# 477.net
KiCad netlist of a schematic drawn in EAGLE
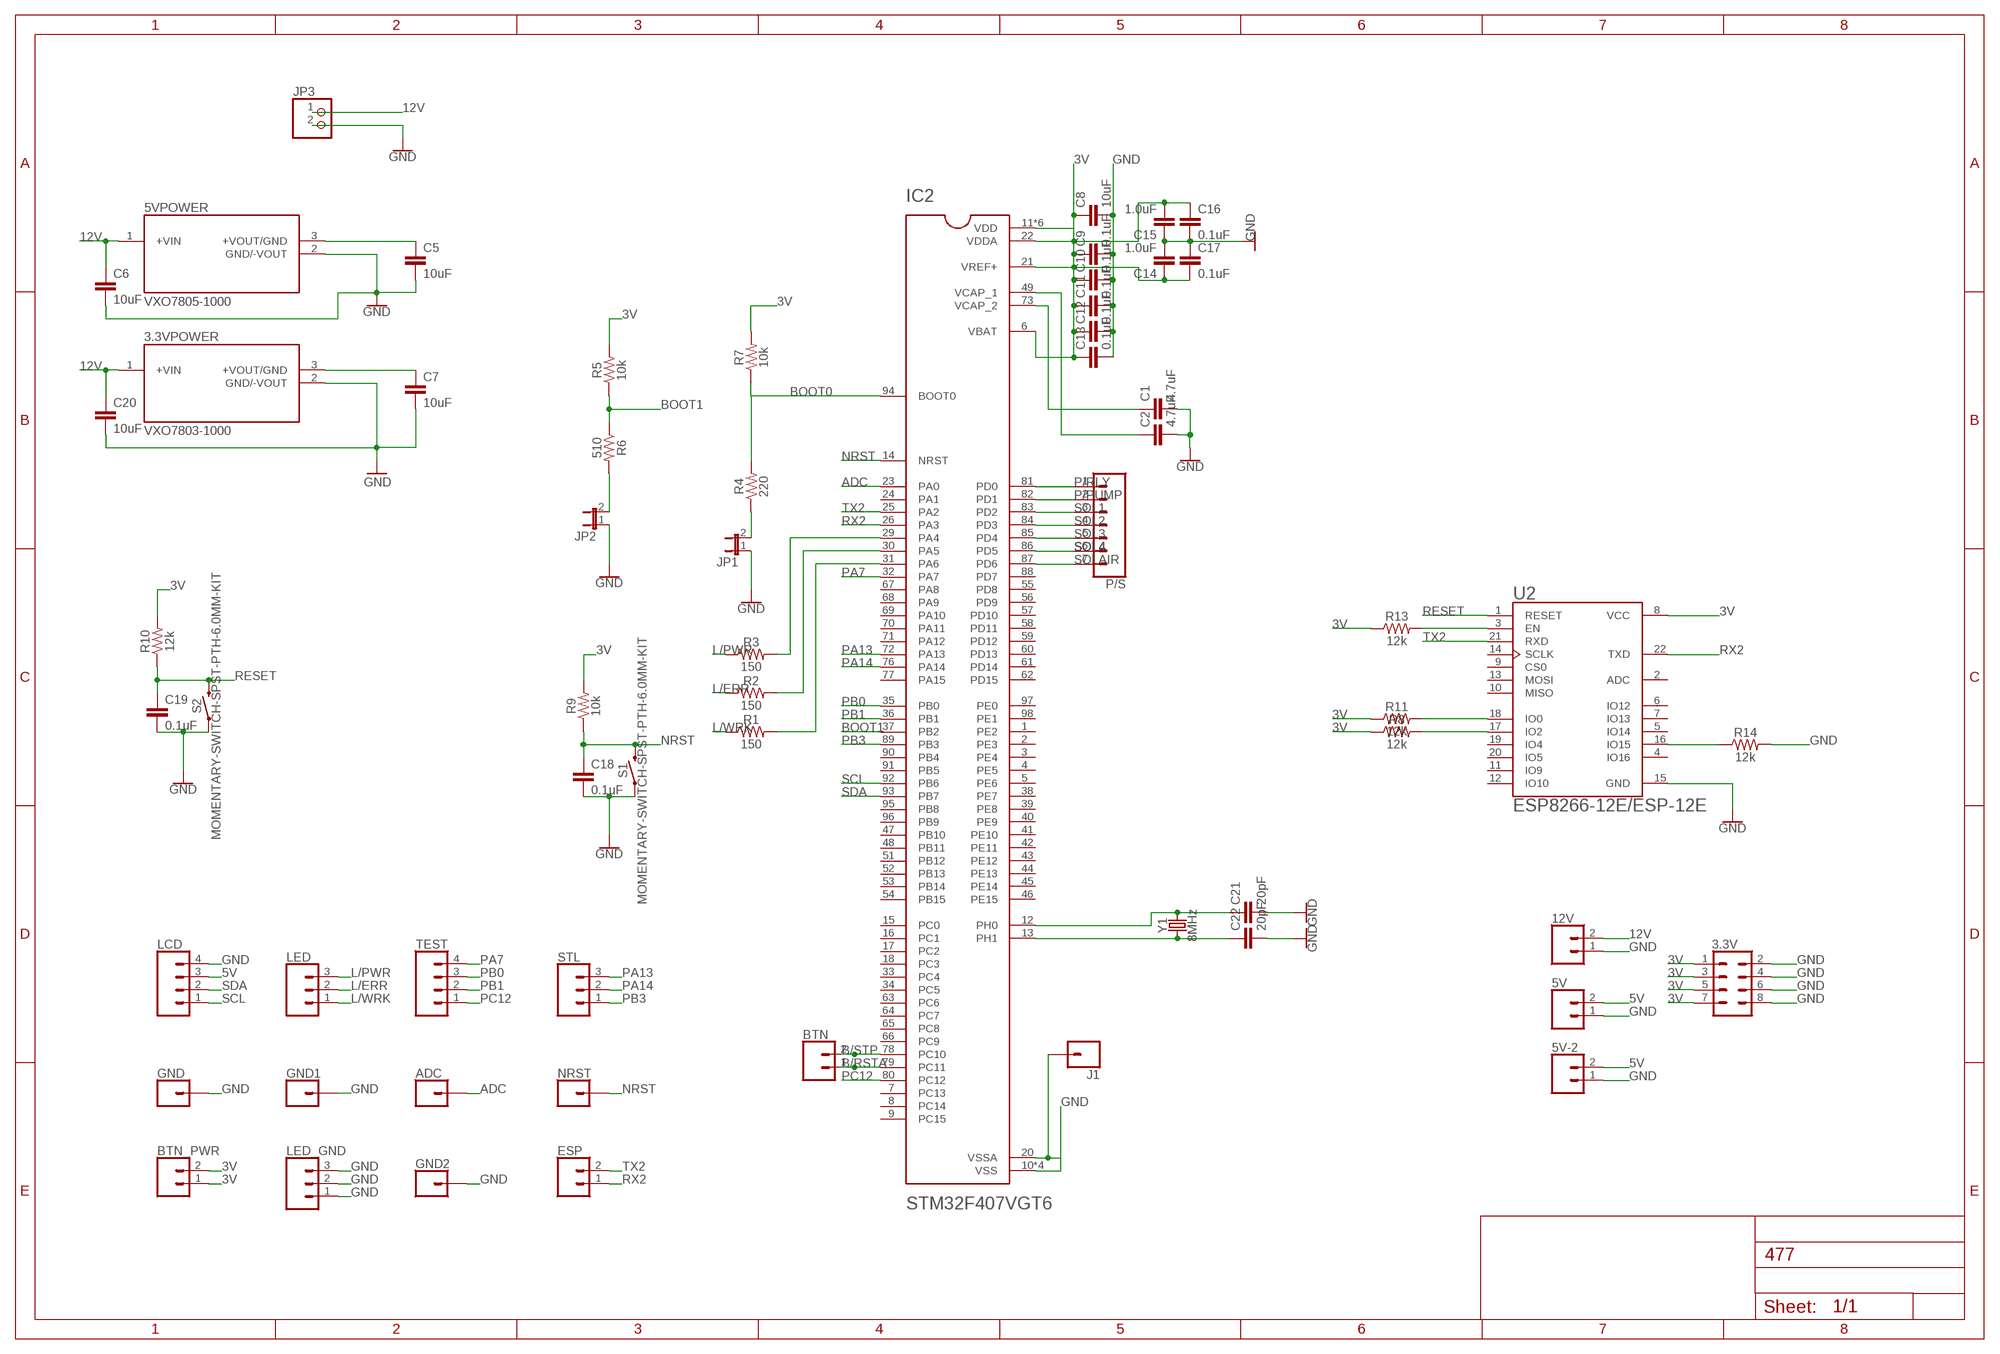
[diagram p0: schematic, sheet 1]

(export (version "E")
  (design (tool "Eeschema 10.0.6"))
  (components
    (comp (ref "3.3V")
      (value "CONN_04X2")
      (footprint "eagle-import:2X4")
      (libsource (lib "eagle-import") (part "CONN_04X2"))
    )
    (comp (ref "3.3VPOWER")
      (value "VXO7803-1000")
      (footprint "eagle-import:CONV_VXO7803-1000")
      (fields (field (name "MF") "CUI Inc."))
      (libsource (lib "eagle-import") (part "VXO7803-1000"))
    )
    (comp (ref "5V")
      (value "CONN_02")
      (footprint "eagle-import:1X02")
      (libsource (lib "eagle-import") (part "SparkFun-Connectors_513_CONN_02"))
    )
    (comp (ref "5V-2")
      (value "CONN_02")
      (footprint "eagle-import:1X02")
      (libsource (lib "eagle-import") (part "SparkFun-Connectors_513_CONN_02"))
    )
    (comp (ref "5VPOWER")
      (value "VXO7805-1000")
      (footprint "eagle-import:CONV_VXO7805-1000")
      (fields (field (name "MF") "CUI Inc."))
      (libsource (lib "eagle-import") (part "VXO7805-1000"))
    )
    (comp (ref "12V")
      (value "CONN_02")
      (footprint "eagle-import:1X02")
      (libsource (lib "eagle-import") (part "SparkFun-Connectors_513_CONN_02"))
    )
    (comp (ref "ADC")
      (value "CONN_01")
      (footprint "eagle-import:1X01")
      (libsource (lib "eagle-import") (part "CONN_01"))
    )
    (comp (ref "BTN")
      (value "CONN_02")
      (footprint "eagle-import:1X02")
      (libsource (lib "eagle-import") (part "CONN_02"))
    )
    (comp (ref "BTN_PWR")
      (value "CONN_02")
      (footprint "eagle-import:1X02")
      (libsource (lib "eagle-import") (part "SparkFun-Connectors_513_CONN_02"))
    )
    (comp (ref "C1")
      (value "4.7uF")
      (footprint "eagle-import:0603")
      (libsource (lib "eagle-import") (part "4.7UF0603"))
    )
    (comp (ref "C2")
      (value "4.7uF")
      (footprint "eagle-import:0603")
      (libsource (lib "eagle-import") (part "4.7UF0603"))
    )
    (comp (ref "C5")
      (value "10uF")
      (footprint "eagle-import:0603")
      (libsource (lib "eagle-import") (part "10UF-0603-6.3V-20%"))
    )
    (comp (ref "C6")
      (value "10uF")
      (footprint "eagle-import:0603")
      (libsource (lib "eagle-import") (part "10UF-0603-6.3V-20%"))
    )
    (comp (ref "C7")
      (value "10uF")
      (footprint "eagle-import:0603")
      (libsource (lib "eagle-import") (part "10UF-0603-6.3V-20%"))
    )
    (comp (ref "C8")
      (value "10uF")
      (footprint "eagle-import:0603")
      (libsource (lib "eagle-import") (part "10UF-0603-6.3V-20%"))
    )
    (comp (ref "C9")
      (value "0.1uF")
      (footprint "eagle-import:0402")
      (libsource (lib "eagle-import") (part "0.1UF-0402-16V-10%"))
    )
    (comp (ref "C10")
      (value "0.1uF")
      (footprint "eagle-import:0402")
      (libsource (lib "eagle-import") (part "0.1UF-0402-16V-10%"))
    )
    (comp (ref "C11")
      (value "0.1uF")
      (footprint "eagle-import:0402")
      (libsource (lib "eagle-import") (part "0.1UF-0402-16V-10%"))
    )
    (comp (ref "C12")
      (value "0.1uF")
      (footprint "eagle-import:0402")
      (libsource (lib "eagle-import") (part "0.1UF-0402-16V-10%"))
    )
    (comp (ref "C13")
      (value "0.1uF")
      (footprint "eagle-import:0402")
      (libsource (lib "eagle-import") (part "0.1UF-0402-16V-10%"))
    )
    (comp (ref "C14")
      (value "1.0uF")
      (footprint "eagle-import:0402")
      (libsource (lib "eagle-import") (part "1.0UF-0402-16V-10%"))
    )
    (comp (ref "C15")
      (value "1.0uF")
      (footprint "eagle-import:0402")
      (libsource (lib "eagle-import") (part "1.0UF-0402-16V-10%"))
    )
    (comp (ref "C16")
      (value "0.1uF")
      (footprint "eagle-import:0402")
      (libsource (lib "eagle-import") (part "0.1UF-0402-16V-10%"))
    )
    (comp (ref "C17")
      (value "0.1uF")
      (footprint "eagle-import:0402")
      (libsource (lib "eagle-import") (part "0.1UF-0402-16V-10%"))
    )
    (comp (ref "C18")
      (value "0.1uF")
      (footprint "eagle-import:0402")
      (libsource (lib "eagle-import") (part "0.1UF-0402-16V-10%"))
    )
    (comp (ref "C19")
      (value "0.1uF")
      (footprint "eagle-import:0402")
      (libsource (lib "eagle-import") (part "0.1UF-0402-16V-10%"))
    )
    (comp (ref "C20")
      (value "10uF")
      (footprint "eagle-import:0603")
      (libsource (lib "eagle-import") (part "10UF-0603-6.3V-20%"))
    )
    (comp (ref "C21")
      (value "20pF")
      (footprint "eagle-import:0603")
      (libsource (lib "eagle-import") (part "18PF-0603-50V-5%"))
    )
    (comp (ref "C22")
      (value "20pF")
      (footprint "eagle-import:0603")
      (libsource (lib "eagle-import") (part "18PF-0603-50V-5%"))
    )
    (comp (ref "ESP")
      (value "CONN_02")
      (footprint "eagle-import:1X02")
      (libsource (lib "eagle-import") (part "SparkFun-Connectors_513_CONN_02"))
    )
    (comp (ref "GND")
      (value "CONN_01PTH_NO_SILK_YES_STOP")
      (footprint "eagle-import:1X01_NO_SILK")
      (libsource (lib "eagle-import") (part "CONN_01PTH_NO_SILK_YES_STOP"))
    )
    (comp (ref "GND1")
      (value "CONN_01PTH_NO_SILK_YES_STOP")
      (footprint "eagle-import:1X01_NO_SILK")
      (libsource (lib "eagle-import") (part "CONN_01PTH_NO_SILK_YES_STOP"))
    )
    (comp (ref "GND2")
      (value "CONN_01")
      (footprint "eagle-import:1X01")
      (libsource (lib "eagle-import") (part "CONN_01"))
    )
    (comp (ref "IC2")
      (value "STM32F407VGT6")
      (footprint "eagle-import:QFP50P1600X1600X160-100N")
      (fields (field (name "MF") "STMicroelectronics"))
      (libsource (lib "eagle-import") (part "STM32F407VGT6"))
    )
    (comp (ref "J1")
      (value "CONN_01PTH_NO_SILK_YES_STOP")
      (footprint "eagle-import:1X01_NO_SILK")
      (libsource (lib "eagle-import") (part "CONN_01PTH_NO_SILK_YES_STOP"))
    )
    (comp (ref "JP1")
      (value "JP1E")
      (footprint "eagle-import:JP1")
      (libsource (lib "eagle-import") (part "JP1E"))
    )
    (comp (ref "JP2")
      (value "JP1E")
      (footprint "eagle-import:JP1")
      (libsource (lib "eagle-import") (part "JP1E"))
    )
    (comp (ref "JP3")
      (value "PINHD-1X2")
      (footprint "eagle-import:1X02")
      (libsource (lib "eagle-import") (part "PINHD-1X2"))
    )
    (comp (ref "LCD")
      (value "CONN_04")
      (footprint "eagle-import:1X04")
      (libsource (lib "eagle-import") (part "CONN_04"))
    )
    (comp (ref "LED")
      (value "CONN_03")
      (footprint "eagle-import:1X03")
      (libsource (lib "eagle-import") (part "CONN_03"))
    )
    (comp (ref "LED_GND")
      (value "CONN_03")
      (footprint "eagle-import:1X03")
      (libsource (lib "eagle-import") (part "CONN_03"))
    )
    (comp (ref "NRST")
      (value "CONN_01")
      (footprint "eagle-import:1X01")
      (libsource (lib "eagle-import") (part "CONN_01"))
    )
    (comp (ref "P/S")
      (value "CONN_07")
      (footprint "eagle-import:1X07")
      (libsource (lib "eagle-import") (part "CONN_07"))
    )
    (comp (ref "R1")
      (value "150")
      (footprint "eagle-import:0603")
      (libsource (lib "eagle-import") (part "150OHM-0603-1/10W-1%"))
    )
    (comp (ref "R2")
      (value "150")
      (footprint "eagle-import:0603")
      (libsource (lib "eagle-import") (part "150OHM-0603-1/10W-1%"))
    )
    (comp (ref "R3")
      (value "150")
      (footprint "eagle-import:0603")
      (libsource (lib "eagle-import") (part "150OHM-0603-1/10W-1%"))
    )
    (comp (ref "R4")
      (value "220")
      (footprint "eagle-import:0603")
      (libsource (lib "eagle-import") (part "220OHM-0603-1/10W-1%"))
    )
    (comp (ref "R5")
      (value "10k")
      (footprint "eagle-import:0603")
      (libsource (lib "eagle-import") (part "1KOHM-0603-1/10W-1%"))
    )
    (comp (ref "R6")
      (value "510")
      (footprint "eagle-import:0603")
      (libsource (lib "eagle-import") (part "0.05OHM-0603-1/5W-1%"))
    )
    (comp (ref "R7")
      (value "10k")
      (footprint "eagle-import:0603")
      (libsource (lib "eagle-import") (part "10KOHM-0603-1/10W-1%"))
    )
    (comp (ref "R8")
      (value "12k")
      (footprint "eagle-import:0603")
      (libsource (lib "eagle-import") (part "12KOHM-0603-1/10W-1%"))
    )
    (comp (ref "R9")
      (value "10k")
      (footprint "eagle-import:0603")
      (libsource (lib "eagle-import") (part "10KOHM-0603-1/10W-1%"))
    )
    (comp (ref "R10")
      (value "12k")
      (footprint "eagle-import:0603")
      (libsource (lib "eagle-import") (part "12KOHM-0603-1/10W-1%"))
    )
    (comp (ref "R11")
      (value "12k")
      (footprint "eagle-import:0603")
      (libsource (lib "eagle-import") (part "12KOHM-0603-1/10W-1%"))
    )
    (comp (ref "R13")
      (value "12k")
      (footprint "eagle-import:0603")
      (libsource (lib "eagle-import") (part "12KOHM-0603-1/10W-1%"))
    )
    (comp (ref "R14")
      (value "12k")
      (footprint "eagle-import:0603")
      (libsource (lib "eagle-import") (part "12KOHM-0603-1/10W-1%"))
    )
    (comp (ref "S1")
      (value "MOMENTARY-SWITCH-SPST-PTH-6.0MM-KIT")
      (footprint "eagle-import:TACTILE_SWITCH_PTH_6.0MM_KIT")
      (libsource (lib "eagle-import") (part "MOMENTARY-SWITCH-SPST-PTH-6.0MM-KIT"))
    )
    (comp (ref "S2")
      (value "MOMENTARY-SWITCH-SPST-PTH-6.0MM-KIT")
      (footprint "eagle-import:TACTILE_SWITCH_PTH_6.0MM_KIT")
      (libsource (lib "eagle-import") (part "MOMENTARY-SWITCH-SPST-PTH-6.0MM-KIT"))
    )
    (comp (ref "STL")
      (value "CONN_03")
      (footprint "eagle-import:1X03")
      (libsource (lib "eagle-import") (part "CONN_03"))
    )
    (comp (ref "TEST")
      (value "CONN_04")
      (footprint "eagle-import:1X04")
      (libsource (lib "eagle-import") (part "CONN_04"))
    )
    (comp (ref "U2")
      (value "ESP8266-12E/ESP-12E")
      (footprint "eagle-import:XCVR_ESP8266-12E_ESP-12E")
      (fields (field (name "MF") "AI-Thinker"))
      (libsource (lib "eagle-import") (part "ESP8266-12E/ESP-12E"))
    )
    (comp (ref "Y1")
      (value "8MHz")
      (footprint "eagle-import:HC49UP")
      (libsource (lib "eagle-import") (part "CRYSTAL-8MHZSMD-HC49UP"))
    )
  )
  (nets
    (net (code "1") (name "/3V") (class "Default")
      (node (ref "3.3V") (pin "1") (pinfunction "1_1") (pintype "passive"))
      (node (ref "3.3V") (pin "3") (pinfunction "3_3") (pintype "passive"))
      (node (ref "3.3V") (pin "5") (pinfunction "5_5") (pintype "passive"))
      (node (ref "3.3V") (pin "7") (pinfunction "7_7") (pintype "passive"))
      (node (ref "3.3VPOWER") (pin "3") (pinfunction "+VOUT/GND_3") (pintype "output"))
      (node (ref "BTN_PWR") (pin "1") (pinfunction "1_1") (pintype "passive"))
      (node (ref "BTN_PWR") (pin "2") (pinfunction "2_2") (pintype "passive"))
      (node (ref "C10") (pin "1") (pinfunction "1_1") (pintype "passive"))
      (node (ref "C11") (pin "1") (pinfunction "1_1") (pintype "passive"))
      (node (ref "C12") (pin "1") (pinfunction "1_1") (pintype "passive"))
      (node (ref "C13") (pin "1") (pinfunction "1_1") (pintype "passive"))
      (node (ref "C14") (pin "1") (pinfunction "1_1") (pintype "passive"))
      (node (ref "C15") (pin "2") (pinfunction "2_2") (pintype "passive"))
      (node (ref "C16") (pin "1") (pinfunction "1_1") (pintype "passive"))
      (node (ref "C17") (pin "2") (pinfunction "2_2") (pintype "passive"))
      (node (ref "C7") (pin "1") (pinfunction "1_1") (pintype "passive"))
      (node (ref "C8") (pin "1") (pinfunction "1_1") (pintype "passive"))
      (node (ref "C9") (pin "1") (pinfunction "1_1") (pintype "passive"))
      (node (ref "IC2") (pin "100") (pinfunction "VDD_100") (pintype "power_in"))
      (node (ref "IC2") (pin "11") (pinfunction "VDD_11") (pintype "power_in"))
      (node (ref "IC2") (pin "19") (pinfunction "VDD_19") (pintype "power_in"))
      (node (ref "IC2") (pin "21") (pinfunction "VREF+_21") (pintype "power_in"))
      (node (ref "IC2") (pin "22") (pinfunction "VDDA_22") (pintype "power_in"))
      (node (ref "IC2") (pin "28") (pinfunction "VDD_28") (pintype "power_in"))
      (node (ref "IC2") (pin "50") (pinfunction "VDD_50") (pintype "power_in"))
      (node (ref "IC2") (pin "6") (pinfunction "VBAT_6") (pintype "power_in"))
      (node (ref "IC2") (pin "75") (pinfunction "VDD_75") (pintype "power_in"))
      (node (ref "R10") (pin "2") (pinfunction "2_2") (pintype "passive"))
      (node (ref "R11") (pin "1") (pinfunction "1_1") (pintype "passive"))
      (node (ref "R13") (pin "1") (pinfunction "1_1") (pintype "passive"))
      (node (ref "R5") (pin "2") (pinfunction "2_2") (pintype "passive"))
      (node (ref "R7") (pin "2") (pinfunction "2_2") (pintype "passive"))
      (node (ref "R8") (pin "1") (pinfunction "1_1") (pintype "passive"))
      (node (ref "R9") (pin "2") (pinfunction "2_2") (pintype "passive"))
      (node (ref "U2") (pin "8") (pinfunction "VCC_8") (pintype "power_in"))
    )
    (net (code "2") (name "/5V") (class "Default")
      (node (ref "5V") (pin "2") (pinfunction "2_2") (pintype "passive"))
      (node (ref "5V-2") (pin "2") (pinfunction "2_2") (pintype "passive"))
      (node (ref "5VPOWER") (pin "3") (pinfunction "+VOUT/GND_3") (pintype "output"))
      (node (ref "C5") (pin "1") (pinfunction "1_1") (pintype "passive"))
      (node (ref "LCD") (pin "3") (pinfunction "3_3") (pintype "passive"))
    )
    (net (code "3") (name "/12V") (class "Default")
      (node (ref "12V") (pin "2") (pinfunction "2_2") (pintype "passive"))
      (node (ref "3.3VPOWER") (pin "1") (pinfunction "+VIN_1") (pintype "input"))
      (node (ref "5VPOWER") (pin "1") (pinfunction "+VIN_1") (pintype "input"))
      (node (ref "C20") (pin "1") (pinfunction "1_1") (pintype "passive"))
      (node (ref "C6") (pin "1") (pinfunction "1_1") (pintype "passive"))
      (node (ref "JP3") (pin "1") (pinfunction "1_1") (pintype "passive"))
    )
    (net (code "4") (name "/ADC") (class "Default")
      (node (ref "ADC") (pin "1") (pinfunction "1_1") (pintype "passive"))
      (node (ref "IC2") (pin "23") (pinfunction "PA0_23") (pintype "bidirectional"))
    )
    (net (code "5") (name "/BOOT0") (class "Default")
      (node (ref "IC2") (pin "94") (pinfunction "BOOT0_94") (pintype "input"))
      (node (ref "R4") (pin "2") (pinfunction "2_2") (pintype "passive"))
      (node (ref "R7") (pin "1") (pinfunction "1_1") (pintype "passive"))
    )
    (net (code "6") (name "/BOOT1") (class "Default")
      (node (ref "IC2") (pin "37") (pinfunction "PB2_37") (pintype "bidirectional"))
      (node (ref "R5") (pin "1") (pinfunction "1_1") (pintype "passive"))
      (node (ref "R6") (pin "1") (pinfunction "1_1") (pintype "passive"))
    )
    (net (code "7") (name "/B{slash}RSTA") (class "Default")
      (node (ref "BTN") (pin "1") (pinfunction "1_1") (pintype "passive"))
      (node (ref "IC2") (pin "79") (pinfunction "PC11_79") (pintype "bidirectional"))
    )
    (net (code "8") (name "/B{slash}STP") (class "Default")
      (node (ref "BTN") (pin "2") (pinfunction "2_2") (pintype "passive"))
      (node (ref "IC2") (pin "78") (pinfunction "PC10_78") (pintype "bidirectional"))
    )
    (net (code "9") (name "/L{slash}ERR") (class "Default")
      (node (ref "LED") (pin "2") (pinfunction "2_2") (pintype "passive"))
      (node (ref "R2") (pin "1") (pinfunction "1_1") (pintype "passive"))
    )
    (net (code "10") (name "/L{slash}PWR") (class "Default")
      (node (ref "LED") (pin "3") (pinfunction "3_3") (pintype "passive"))
      (node (ref "R3") (pin "1") (pinfunction "1_1") (pintype "passive"))
    )
    (net (code "11") (name "/L{slash}WRK") (class "Default")
      (node (ref "LED") (pin "1") (pinfunction "1_1") (pintype "passive"))
      (node (ref "R1") (pin "1") (pinfunction "1_1") (pintype "passive"))
    )
    (net (code "12") (name "/NRST") (class "Default")
      (node (ref "C18") (pin "1") (pinfunction "1_1") (pintype "passive"))
      (node (ref "IC2") (pin "14") (pinfunction "NRST_14") (pintype "bidirectional"))
      (node (ref "NRST") (pin "1") (pinfunction "1_1") (pintype "passive"))
      (node (ref "R9") (pin "1") (pinfunction "1_1") (pintype "passive"))
      (node (ref "S1") (pin "3") (pinfunction "2_3") (pintype "passive"))
    )
    (net (code "13") (name "/PA7") (class "Default")
      (node (ref "IC2") (pin "32") (pinfunction "PA7_32") (pintype "bidirectional"))
      (node (ref "TEST") (pin "4") (pinfunction "4_4") (pintype "passive"))
    )
    (net (code "14") (name "/PA13") (class "Default")
      (node (ref "IC2") (pin "72") (pinfunction "PA13_72") (pintype "bidirectional"))
      (node (ref "STL") (pin "3") (pinfunction "3_3") (pintype "passive"))
    )
    (net (code "15") (name "/PA14") (class "Default")
      (node (ref "IC2") (pin "76") (pinfunction "PA14_76") (pintype "bidirectional"))
      (node (ref "STL") (pin "2") (pinfunction "2_2") (pintype "passive"))
    )
    (net (code "16") (name "/PB0") (class "Default")
      (node (ref "IC2") (pin "35") (pinfunction "PB0_35") (pintype "bidirectional"))
      (node (ref "TEST") (pin "3") (pinfunction "3_3") (pintype "passive"))
    )
    (net (code "17") (name "/PB1") (class "Default")
      (node (ref "IC2") (pin "36") (pinfunction "PB1_36") (pintype "bidirectional"))
      (node (ref "TEST") (pin "2") (pinfunction "2_2") (pintype "passive"))
    )
    (net (code "18") (name "/PB3") (class "Default")
      (node (ref "IC2") (pin "89") (pinfunction "PB3_89") (pintype "bidirectional"))
      (node (ref "STL") (pin "1") (pinfunction "1_1") (pintype "passive"))
    )
    (net (code "19") (name "/PC12") (class "Default")
      (node (ref "IC2") (pin "80") (pinfunction "PC12_80") (pintype "bidirectional"))
      (node (ref "TEST") (pin "1") (pinfunction "1_1") (pintype "passive"))
    )
    (net (code "20") (name "/P{slash}PUMP") (class "Default")
      (node (ref "IC2") (pin "82") (pinfunction "PD1_82") (pintype "bidirectional"))
      (node (ref "P/S") (pin "2") (pinfunction "2_2") (pintype "passive"))
    )
    (net (code "21") (name "/P{slash}RLY") (class "Default")
      (node (ref "IC2") (pin "81") (pinfunction "PD0_81") (pintype "bidirectional"))
      (node (ref "P/S") (pin "1") (pinfunction "1_1") (pintype "passive"))
    )
    (net (code "22") (name "/RESET") (class "Default")
      (node (ref "C19") (pin "1") (pinfunction "1_1") (pintype "passive"))
      (node (ref "R10") (pin "1") (pinfunction "1_1") (pintype "passive"))
      (node (ref "S2") (pin "3") (pinfunction "2_3") (pintype "passive"))
      (node (ref "U2") (pin "1") (pinfunction "RESET_1") (pintype "input"))
    )
    (net (code "23") (name "/RX2") (class "Default")
      (node (ref "ESP") (pin "1") (pinfunction "1_1") (pintype "passive"))
      (node (ref "IC2") (pin "26") (pinfunction "PA3_26") (pintype "bidirectional"))
      (node (ref "U2") (pin "22") (pinfunction "TXD_22") (pintype "output"))
    )
    (net (code "24") (name "/SCL") (class "Default")
      (node (ref "IC2") (pin "92") (pinfunction "PB6_92") (pintype "bidirectional"))
      (node (ref "LCD") (pin "1") (pinfunction "1_1") (pintype "passive"))
    )
    (net (code "25") (name "/SDA") (class "Default")
      (node (ref "IC2") (pin "93") (pinfunction "PB7_93") (pintype "bidirectional"))
      (node (ref "LCD") (pin "2") (pinfunction "2_2") (pintype "passive"))
    )
    (net (code "26") (name "/SOL1") (class "Default")
      (node (ref "IC2") (pin "83") (pinfunction "PD2_83") (pintype "bidirectional"))
      (node (ref "P/S") (pin "3") (pinfunction "3_3") (pintype "passive"))
    )
    (net (code "27") (name "/SOL2") (class "Default")
      (node (ref "IC2") (pin "84") (pinfunction "PD3_84") (pintype "bidirectional"))
      (node (ref "P/S") (pin "4") (pinfunction "4_4") (pintype "passive"))
    )
    (net (code "28") (name "/SOL3") (class "Default")
      (node (ref "IC2") (pin "85") (pinfunction "PD4_85") (pintype "bidirectional"))
      (node (ref "P/S") (pin "5") (pinfunction "5_5") (pintype "passive"))
    )
    (net (code "29") (name "/SOL4") (class "Default")
      (node (ref "IC2") (pin "86") (pinfunction "PD5_86") (pintype "bidirectional"))
      (node (ref "P/S") (pin "6") (pinfunction "6_6") (pintype "passive"))
    )
    (net (code "30") (name "/SOLAIR") (class "Default")
      (node (ref "IC2") (pin "87") (pinfunction "PD6_87") (pintype "bidirectional"))
      (node (ref "P/S") (pin "7") (pinfunction "7_7") (pintype "passive"))
    )
    (net (code "31") (name "/TX2") (class "Default")
      (node (ref "ESP") (pin "2") (pinfunction "2_2") (pintype "passive"))
      (node (ref "IC2") (pin "25") (pinfunction "PA2_25") (pintype "bidirectional"))
      (node (ref "U2") (pin "21") (pinfunction "RXD_21") (pintype "input"))
    )
    (net (code "32") (name "GND") (class "Default")
      (node (ref "12V") (pin "1") (pinfunction "1_1") (pintype "passive"))
      (node (ref "3.3V") (pin "2") (pinfunction "2_2") (pintype "passive"))
      (node (ref "3.3V") (pin "4") (pinfunction "4_4") (pintype "passive"))
      (node (ref "3.3V") (pin "6") (pinfunction "6_6") (pintype "passive"))
      (node (ref "3.3V") (pin "8") (pinfunction "8_8") (pintype "passive"))
      (node (ref "3.3VPOWER") (pin "2") (pinfunction "GND/-VOUT_2") (pintype "output"))
      (node (ref "5V") (pin "1") (pinfunction "1_1") (pintype "passive"))
      (node (ref "5V-2") (pin "1") (pinfunction "1_1") (pintype "passive"))
      (node (ref "5VPOWER") (pin "2") (pinfunction "GND/-VOUT_2") (pintype "output"))
      (node (ref "C1") (pin "2") (pinfunction "2_2") (pintype "passive"))
      (node (ref "C10") (pin "2") (pinfunction "2_2") (pintype "passive"))
      (node (ref "C11") (pin "2") (pinfunction "2_2") (pintype "passive"))
      (node (ref "C12") (pin "2") (pinfunction "2_2") (pintype "passive"))
      (node (ref "C13") (pin "2") (pinfunction "2_2") (pintype "passive"))
      (node (ref "C14") (pin "2") (pinfunction "2_2") (pintype "passive"))
      (node (ref "C15") (pin "1") (pinfunction "1_1") (pintype "passive"))
      (node (ref "C16") (pin "2") (pinfunction "2_2") (pintype "passive"))
      (node (ref "C17") (pin "1") (pinfunction "1_1") (pintype "passive"))
      (node (ref "C18") (pin "2") (pinfunction "2_2") (pintype "passive"))
      (node (ref "C19") (pin "2") (pinfunction "2_2") (pintype "passive"))
      (node (ref "C2") (pin "2") (pinfunction "2_2") (pintype "passive"))
      (node (ref "C20") (pin "2") (pinfunction "2_2") (pintype "passive"))
      (node (ref "C21") (pin "2") (pinfunction "2_2") (pintype "passive"))
      (node (ref "C22") (pin "2") (pinfunction "2_2") (pintype "passive"))
      (node (ref "C5") (pin "2") (pinfunction "2_2") (pintype "passive"))
      (node (ref "C6") (pin "2") (pinfunction "2_2") (pintype "passive"))
      (node (ref "C7") (pin "2") (pinfunction "2_2") (pintype "passive"))
      (node (ref "C8") (pin "2") (pinfunction "2_2") (pintype "passive"))
      (node (ref "C9") (pin "2") (pinfunction "2_2") (pintype "passive"))
      (node (ref "GND") (pin "1") (pinfunction "1_1") (pintype "passive"))
      (node (ref "GND1") (pin "1") (pinfunction "1_1") (pintype "passive"))
      (node (ref "GND2") (pin "1") (pinfunction "1_1") (pintype "passive"))
      (node (ref "IC2") (pin "10") (pinfunction "VSS_10") (pintype "passive"))
      (node (ref "IC2") (pin "27") (pinfunction "VSS_27") (pintype "passive"))
      (node (ref "IC2") (pin "74") (pinfunction "VSS_74") (pintype "passive"))
      (node (ref "IC2") (pin "99") (pinfunction "VSS_99") (pintype "passive"))
      (node (ref "JP1") (pin "1") (pinfunction "1_1") (pintype "passive"))
      (node (ref "JP2") (pin "1") (pinfunction "1_1") (pintype "passive"))
      (node (ref "JP3") (pin "2") (pinfunction "2_2") (pintype "passive"))
      (node (ref "LCD") (pin "4") (pinfunction "4_4") (pintype "passive"))
      (node (ref "LED_GND") (pin "1") (pinfunction "1_1") (pintype "passive"))
      (node (ref "LED_GND") (pin "2") (pinfunction "2_2") (pintype "passive"))
      (node (ref "LED_GND") (pin "3") (pinfunction "3_3") (pintype "passive"))
      (node (ref "R14") (pin "2") (pinfunction "2_2") (pintype "passive"))
      (node (ref "S1") (pin "1") (pinfunction "1_1") (pintype "passive"))
      (node (ref "S2") (pin "1") (pinfunction "1_1") (pintype "passive"))
      (node (ref "U2") (pin "15") (pinfunction "GND_15") (pintype "power_in"))
    )
    (net (code "33") (name "Net-(IC2-PA4)") (class "Default")
      (node (ref "IC2") (pin "29") (pinfunction "PA4_29") (pintype "bidirectional"))
      (node (ref "R3") (pin "2") (pinfunction "2_2") (pintype "passive"))
    )
    (net (code "34") (name "Net-(IC2-PA5)") (class "Default")
      (node (ref "IC2") (pin "30") (pinfunction "PA5_30") (pintype "bidirectional"))
      (node (ref "R2") (pin "2") (pinfunction "2_2") (pintype "passive"))
    )
    (net (code "35") (name "Net-(IC2-PA6)") (class "Default")
      (node (ref "IC2") (pin "31") (pinfunction "PA6_31") (pintype "bidirectional"))
      (node (ref "R1") (pin "2") (pinfunction "2_2") (pintype "passive"))
    )
    (net (code "36") (name "Net-(IC2-PH0)") (class "Default")
      (node (ref "C21") (pin "1") (pinfunction "1_1") (pintype "passive"))
      (node (ref "IC2") (pin "12") (pinfunction "PH0_12") (pintype "bidirectional"))
      (node (ref "Y1") (pin "2") (pinfunction "2_2") (pintype "passive"))
    )
    (net (code "37") (name "Net-(IC2-PH1)") (class "Default")
      (node (ref "C22") (pin "1") (pinfunction "1_1") (pintype "passive"))
      (node (ref "IC2") (pin "13") (pinfunction "PH1_13") (pintype "bidirectional"))
      (node (ref "Y1") (pin "1") (pinfunction "1_1") (pintype "passive"))
    )
    (net (code "38") (name "Net-(IC2-VCAP_1)") (class "Default")
      (node (ref "C2") (pin "1") (pinfunction "1_1") (pintype "passive"))
      (node (ref "IC2") (pin "49") (pinfunction "VCAP_1_49") (pintype "power_in"))
    )
    (net (code "39") (name "Net-(IC2-VCAP_2)") (class "Default")
      (node (ref "C1") (pin "1") (pinfunction "1_1") (pintype "passive"))
      (node (ref "IC2") (pin "73") (pinfunction "VCAP_2_73") (pintype "power_in"))
    )
    (net (code "40") (name "Net-(IC2-VSSA)") (class "Default")
      (node (ref "IC2") (pin "20") (pinfunction "VSSA_20") (pintype "passive"))
      (node (ref "J1") (pin "1") (pinfunction "1_1") (pintype "passive"))
    )
    (net (code "41") (name "Net-(JP1-Pad2)") (class "Default")
      (node (ref "JP1") (pin "2") (pinfunction "2_2") (pintype "passive"))
      (node (ref "R4") (pin "1") (pinfunction "1_1") (pintype "passive"))
    )
    (net (code "42") (name "Net-(JP2-Pad2)") (class "Default")
      (node (ref "JP2") (pin "2") (pinfunction "2_2") (pintype "passive"))
      (node (ref "R6") (pin "2") (pinfunction "2_2") (pintype "passive"))
    )
    (net (code "43") (name "Net-(U2-EN)") (class "Default")
      (node (ref "R13") (pin "2") (pinfunction "2_2") (pintype "passive"))
      (node (ref "U2") (pin "3") (pinfunction "EN_3") (pintype "input"))
    )
    (net (code "44") (name "Net-(U2-IO0)") (class "Default")
      (node (ref "R11") (pin "2") (pinfunction "2_2") (pintype "passive"))
      (node (ref "U2") (pin "18") (pinfunction "IO0_18") (pintype "bidirectional"))
    )
    (net (code "45") (name "Net-(U2-IO2)") (class "Default")
      (node (ref "R8") (pin "2") (pinfunction "2_2") (pintype "passive"))
      (node (ref "U2") (pin "17") (pinfunction "IO2_17") (pintype "bidirectional"))
    )
    (net (code "46") (name "Net-(U2-IO15)") (class "Default")
      (node (ref "R14") (pin "1") (pinfunction "1_1") (pintype "passive"))
      (node (ref "U2") (pin "16") (pinfunction "IO15_16") (pintype "bidirectional"))
    )
    (net (code "47") (name "unconnected-(IC2-PA1-Pad24)") (class "Default")
      (node (ref "IC2") (pin "24") (pinfunction "PA1_24") (pintype "bidirectional"))
    )
    (net (code "48") (name "unconnected-(IC2-PA8-Pad67)") (class "Default")
      (node (ref "IC2") (pin "67") (pinfunction "PA8_67") (pintype "bidirectional"))
    )
    (net (code "49") (name "unconnected-(IC2-PA9-Pad68)") (class "Default")
      (node (ref "IC2") (pin "68") (pinfunction "PA9_68") (pintype "bidirectional"))
    )
    (net (code "50") (name "unconnected-(IC2-PA10-Pad69)") (class "Default")
      (node (ref "IC2") (pin "69") (pinfunction "PA10_69") (pintype "bidirectional"))
    )
    (net (code "51") (name "unconnected-(IC2-PA11-Pad70)") (class "Default")
      (node (ref "IC2") (pin "70") (pinfunction "PA11_70") (pintype "bidirectional"))
    )
    (net (code "52") (name "unconnected-(IC2-PA12-Pad71)") (class "Default")
      (node (ref "IC2") (pin "71") (pinfunction "PA12_71") (pintype "bidirectional"))
    )
    (net (code "53") (name "unconnected-(IC2-PA15-Pad77)") (class "Default")
      (node (ref "IC2") (pin "77") (pinfunction "PA15_77") (pintype "bidirectional"))
    )
    (net (code "54") (name "unconnected-(IC2-PB4-Pad90)") (class "Default")
      (node (ref "IC2") (pin "90") (pinfunction "PB4_90") (pintype "bidirectional"))
    )
    (net (code "55") (name "unconnected-(IC2-PB5-Pad91)") (class "Default")
      (node (ref "IC2") (pin "91") (pinfunction "PB5_91") (pintype "bidirectional"))
    )
    (net (code "56") (name "unconnected-(IC2-PB8-Pad95)") (class "Default")
      (node (ref "IC2") (pin "95") (pinfunction "PB8_95") (pintype "bidirectional"))
    )
    (net (code "57") (name "unconnected-(IC2-PB9-Pad96)") (class "Default")
      (node (ref "IC2") (pin "96") (pinfunction "PB9_96") (pintype "bidirectional"))
    )
    (net (code "58") (name "unconnected-(IC2-PB10-Pad47)") (class "Default")
      (node (ref "IC2") (pin "47") (pinfunction "PB10_47") (pintype "bidirectional"))
    )
    (net (code "59") (name "unconnected-(IC2-PB11-Pad48)") (class "Default")
      (node (ref "IC2") (pin "48") (pinfunction "PB11_48") (pintype "bidirectional"))
    )
    (net (code "60") (name "unconnected-(IC2-PB12-Pad51)") (class "Default")
      (node (ref "IC2") (pin "51") (pinfunction "PB12_51") (pintype "bidirectional"))
    )
    (net (code "61") (name "unconnected-(IC2-PB13-Pad52)") (class "Default")
      (node (ref "IC2") (pin "52") (pinfunction "PB13_52") (pintype "bidirectional"))
    )
    (net (code "62") (name "unconnected-(IC2-PB14-Pad53)") (class "Default")
      (node (ref "IC2") (pin "53") (pinfunction "PB14_53") (pintype "bidirectional"))
    )
    (net (code "63") (name "unconnected-(IC2-PB15-Pad54)") (class "Default")
      (node (ref "IC2") (pin "54") (pinfunction "PB15_54") (pintype "bidirectional"))
    )
    (net (code "64") (name "unconnected-(IC2-PC0-Pad15)") (class "Default")
      (node (ref "IC2") (pin "15") (pinfunction "PC0_15") (pintype "bidirectional"))
    )
    (net (code "65") (name "unconnected-(IC2-PC1-Pad16)") (class "Default")
      (node (ref "IC2") (pin "16") (pinfunction "PC1_16") (pintype "bidirectional"))
    )
    (net (code "66") (name "unconnected-(IC2-PC2-Pad17)") (class "Default")
      (node (ref "IC2") (pin "17") (pinfunction "PC2_17") (pintype "bidirectional"))
    )
    (net (code "67") (name "unconnected-(IC2-PC3-Pad18)") (class "Default")
      (node (ref "IC2") (pin "18") (pinfunction "PC3_18") (pintype "bidirectional"))
    )
    (net (code "68") (name "unconnected-(IC2-PC4-Pad33)") (class "Default")
      (node (ref "IC2") (pin "33") (pinfunction "PC4_33") (pintype "bidirectional"))
    )
    (net (code "69") (name "unconnected-(IC2-PC5-Pad34)") (class "Default")
      (node (ref "IC2") (pin "34") (pinfunction "PC5_34") (pintype "bidirectional"))
    )
    (net (code "70") (name "unconnected-(IC2-PC6-Pad63)") (class "Default")
      (node (ref "IC2") (pin "63") (pinfunction "PC6_63") (pintype "bidirectional"))
    )
    (net (code "71") (name "unconnected-(IC2-PC7-Pad64)") (class "Default")
      (node (ref "IC2") (pin "64") (pinfunction "PC7_64") (pintype "bidirectional"))
    )
    (net (code "72") (name "unconnected-(IC2-PC8-Pad65)") (class "Default")
      (node (ref "IC2") (pin "65") (pinfunction "PC8_65") (pintype "bidirectional"))
    )
    (net (code "73") (name "unconnected-(IC2-PC9-Pad66)") (class "Default")
      (node (ref "IC2") (pin "66") (pinfunction "PC9_66") (pintype "bidirectional"))
    )
    (net (code "74") (name "unconnected-(IC2-PC13-Pad7)") (class "Default")
      (node (ref "IC2") (pin "7") (pinfunction "PC13_7") (pintype "bidirectional"))
    )
    (net (code "75") (name "unconnected-(IC2-PC14-Pad8)") (class "Default")
      (node (ref "IC2") (pin "8") (pinfunction "PC14_8") (pintype "bidirectional"))
    )
    (net (code "76") (name "unconnected-(IC2-PC15-Pad9)") (class "Default")
      (node (ref "IC2") (pin "9") (pinfunction "PC15_9") (pintype "bidirectional"))
    )
    (net (code "77") (name "unconnected-(IC2-PD7-Pad88)") (class "Default")
      (node (ref "IC2") (pin "88") (pinfunction "PD7_88") (pintype "bidirectional"))
    )
    (net (code "78") (name "unconnected-(IC2-PD8-Pad55)") (class "Default")
      (node (ref "IC2") (pin "55") (pinfunction "PD8_55") (pintype "bidirectional"))
    )
    (net (code "79") (name "unconnected-(IC2-PD9-Pad56)") (class "Default")
      (node (ref "IC2") (pin "56") (pinfunction "PD9_56") (pintype "bidirectional"))
    )
    (net (code "80") (name "unconnected-(IC2-PD10-Pad57)") (class "Default")
      (node (ref "IC2") (pin "57") (pinfunction "PD10_57") (pintype "bidirectional"))
    )
    (net (code "81") (name "unconnected-(IC2-PD11-Pad58)") (class "Default")
      (node (ref "IC2") (pin "58") (pinfunction "PD11_58") (pintype "bidirectional"))
    )
    (net (code "82") (name "unconnected-(IC2-PD12-Pad59)") (class "Default")
      (node (ref "IC2") (pin "59") (pinfunction "PD12_59") (pintype "bidirectional"))
    )
    (net (code "83") (name "unconnected-(IC2-PD13-Pad60)") (class "Default")
      (node (ref "IC2") (pin "60") (pinfunction "PD13_60") (pintype "bidirectional"))
    )
    (net (code "84") (name "unconnected-(IC2-PD14-Pad61)") (class "Default")
      (node (ref "IC2") (pin "61") (pinfunction "PD14_61") (pintype "bidirectional"))
    )
    (net (code "85") (name "unconnected-(IC2-PD15-Pad62)") (class "Default")
      (node (ref "IC2") (pin "62") (pinfunction "PD15_62") (pintype "bidirectional"))
    )
    (net (code "86") (name "unconnected-(IC2-PE0-Pad97)") (class "Default")
      (node (ref "IC2") (pin "97") (pinfunction "PE0_97") (pintype "bidirectional"))
    )
    (net (code "87") (name "unconnected-(IC2-PE1-Pad98)") (class "Default")
      (node (ref "IC2") (pin "98") (pinfunction "PE1_98") (pintype "bidirectional"))
    )
    (net (code "88") (name "unconnected-(IC2-PE2-Pad1)") (class "Default")
      (node (ref "IC2") (pin "1") (pinfunction "PE2_1") (pintype "bidirectional"))
    )
    (net (code "89") (name "unconnected-(IC2-PE3-Pad2)") (class "Default")
      (node (ref "IC2") (pin "2") (pinfunction "PE3_2") (pintype "bidirectional"))
    )
    (net (code "90") (name "unconnected-(IC2-PE4-Pad3)") (class "Default")
      (node (ref "IC2") (pin "3") (pinfunction "PE4_3") (pintype "bidirectional"))
    )
    (net (code "91") (name "unconnected-(IC2-PE5-Pad4)") (class "Default")
      (node (ref "IC2") (pin "4") (pinfunction "PE5_4") (pintype "bidirectional"))
    )
    (net (code "92") (name "unconnected-(IC2-PE6-Pad5)") (class "Default")
      (node (ref "IC2") (pin "5") (pinfunction "PE6_5") (pintype "bidirectional"))
    )
    (net (code "93") (name "unconnected-(IC2-PE7-Pad38)") (class "Default")
      (node (ref "IC2") (pin "38") (pinfunction "PE7_38") (pintype "bidirectional"))
    )
    (net (code "94") (name "unconnected-(IC2-PE8-Pad39)") (class "Default")
      (node (ref "IC2") (pin "39") (pinfunction "PE8_39") (pintype "bidirectional"))
    )
    (net (code "95") (name "unconnected-(IC2-PE9-Pad40)") (class "Default")
      (node (ref "IC2") (pin "40") (pinfunction "PE9_40") (pintype "bidirectional"))
    )
    (net (code "96") (name "unconnected-(IC2-PE10-Pad41)") (class "Default")
      (node (ref "IC2") (pin "41") (pinfunction "PE10_41") (pintype "bidirectional"))
    )
    (net (code "97") (name "unconnected-(IC2-PE11-Pad42)") (class "Default")
      (node (ref "IC2") (pin "42") (pinfunction "PE11_42") (pintype "bidirectional"))
    )
    (net (code "98") (name "unconnected-(IC2-PE12-Pad43)") (class "Default")
      (node (ref "IC2") (pin "43") (pinfunction "PE12_43") (pintype "bidirectional"))
    )
    (net (code "99") (name "unconnected-(IC2-PE13-Pad44)") (class "Default")
      (node (ref "IC2") (pin "44") (pinfunction "PE13_44") (pintype "bidirectional"))
    )
    (net (code "100") (name "unconnected-(IC2-PE14-Pad45)") (class "Default")
      (node (ref "IC2") (pin "45") (pinfunction "PE14_45") (pintype "bidirectional"))
    )
    (net (code "101") (name "unconnected-(IC2-PE15-Pad46)") (class "Default")
      (node (ref "IC2") (pin "46") (pinfunction "PE15_46") (pintype "bidirectional"))
    )
    (net (code "102") (name "unconnected-(U2-ADC-Pad2)") (class "Default")
      (node (ref "U2") (pin "2") (pinfunction "ADC_2") (pintype "passive"))
    )
    (net (code "103") (name "unconnected-(U2-CS0-Pad9)") (class "Default")
      (node (ref "U2") (pin "9") (pinfunction "CS0_9") (pintype "input"))
    )
    (net (code "104") (name "unconnected-(U2-IO4-Pad19)") (class "Default")
      (node (ref "U2") (pin "19") (pinfunction "IO4_19") (pintype "bidirectional"))
    )
    (net (code "105") (name "unconnected-(U2-IO5-Pad20)") (class "Default")
      (node (ref "U2") (pin "20") (pinfunction "IO5_20") (pintype "bidirectional"))
    )
    (net (code "106") (name "unconnected-(U2-IO9-Pad11)") (class "Default")
      (node (ref "U2") (pin "11") (pinfunction "IO9_11") (pintype "bidirectional"))
    )
    (net (code "107") (name "unconnected-(U2-IO10-Pad12)") (class "Default")
      (node (ref "U2") (pin "12") (pinfunction "IO10_12") (pintype "bidirectional"))
    )
    (net (code "108") (name "unconnected-(U2-IO12-Pad6)") (class "Default")
      (node (ref "U2") (pin "6") (pinfunction "IO12_6") (pintype "bidirectional"))
    )
    (net (code "109") (name "unconnected-(U2-IO13-Pad7)") (class "Default")
      (node (ref "U2") (pin "7") (pinfunction "IO13_7") (pintype "bidirectional"))
    )
    (net (code "110") (name "unconnected-(U2-IO14-Pad5)") (class "Default")
      (node (ref "U2") (pin "5") (pinfunction "IO14_5") (pintype "bidirectional"))
    )
    (net (code "111") (name "unconnected-(U2-IO16-Pad4)") (class "Default")
      (node (ref "U2") (pin "4") (pinfunction "IO16_4") (pintype "bidirectional"))
    )
    (net (code "112") (name "unconnected-(U2-MISO-Pad10)") (class "Default")
      (node (ref "U2") (pin "10") (pinfunction "MISO_10") (pintype "bidirectional"))
    )
    (net (code "113") (name "unconnected-(U2-MOSI-Pad13)") (class "Default")
      (node (ref "U2") (pin "13") (pinfunction "MOSI_13") (pintype "bidirectional"))
    )
    (net (code "114") (name "unconnected-(U2-SCLK-Pad14)") (class "Default")
      (node (ref "U2") (pin "14") (pinfunction "SCLK_14") (pintype "input"))
    )
  )
)
